# latch6.net
KiCad netlist of a schematic drawn in EAGLE
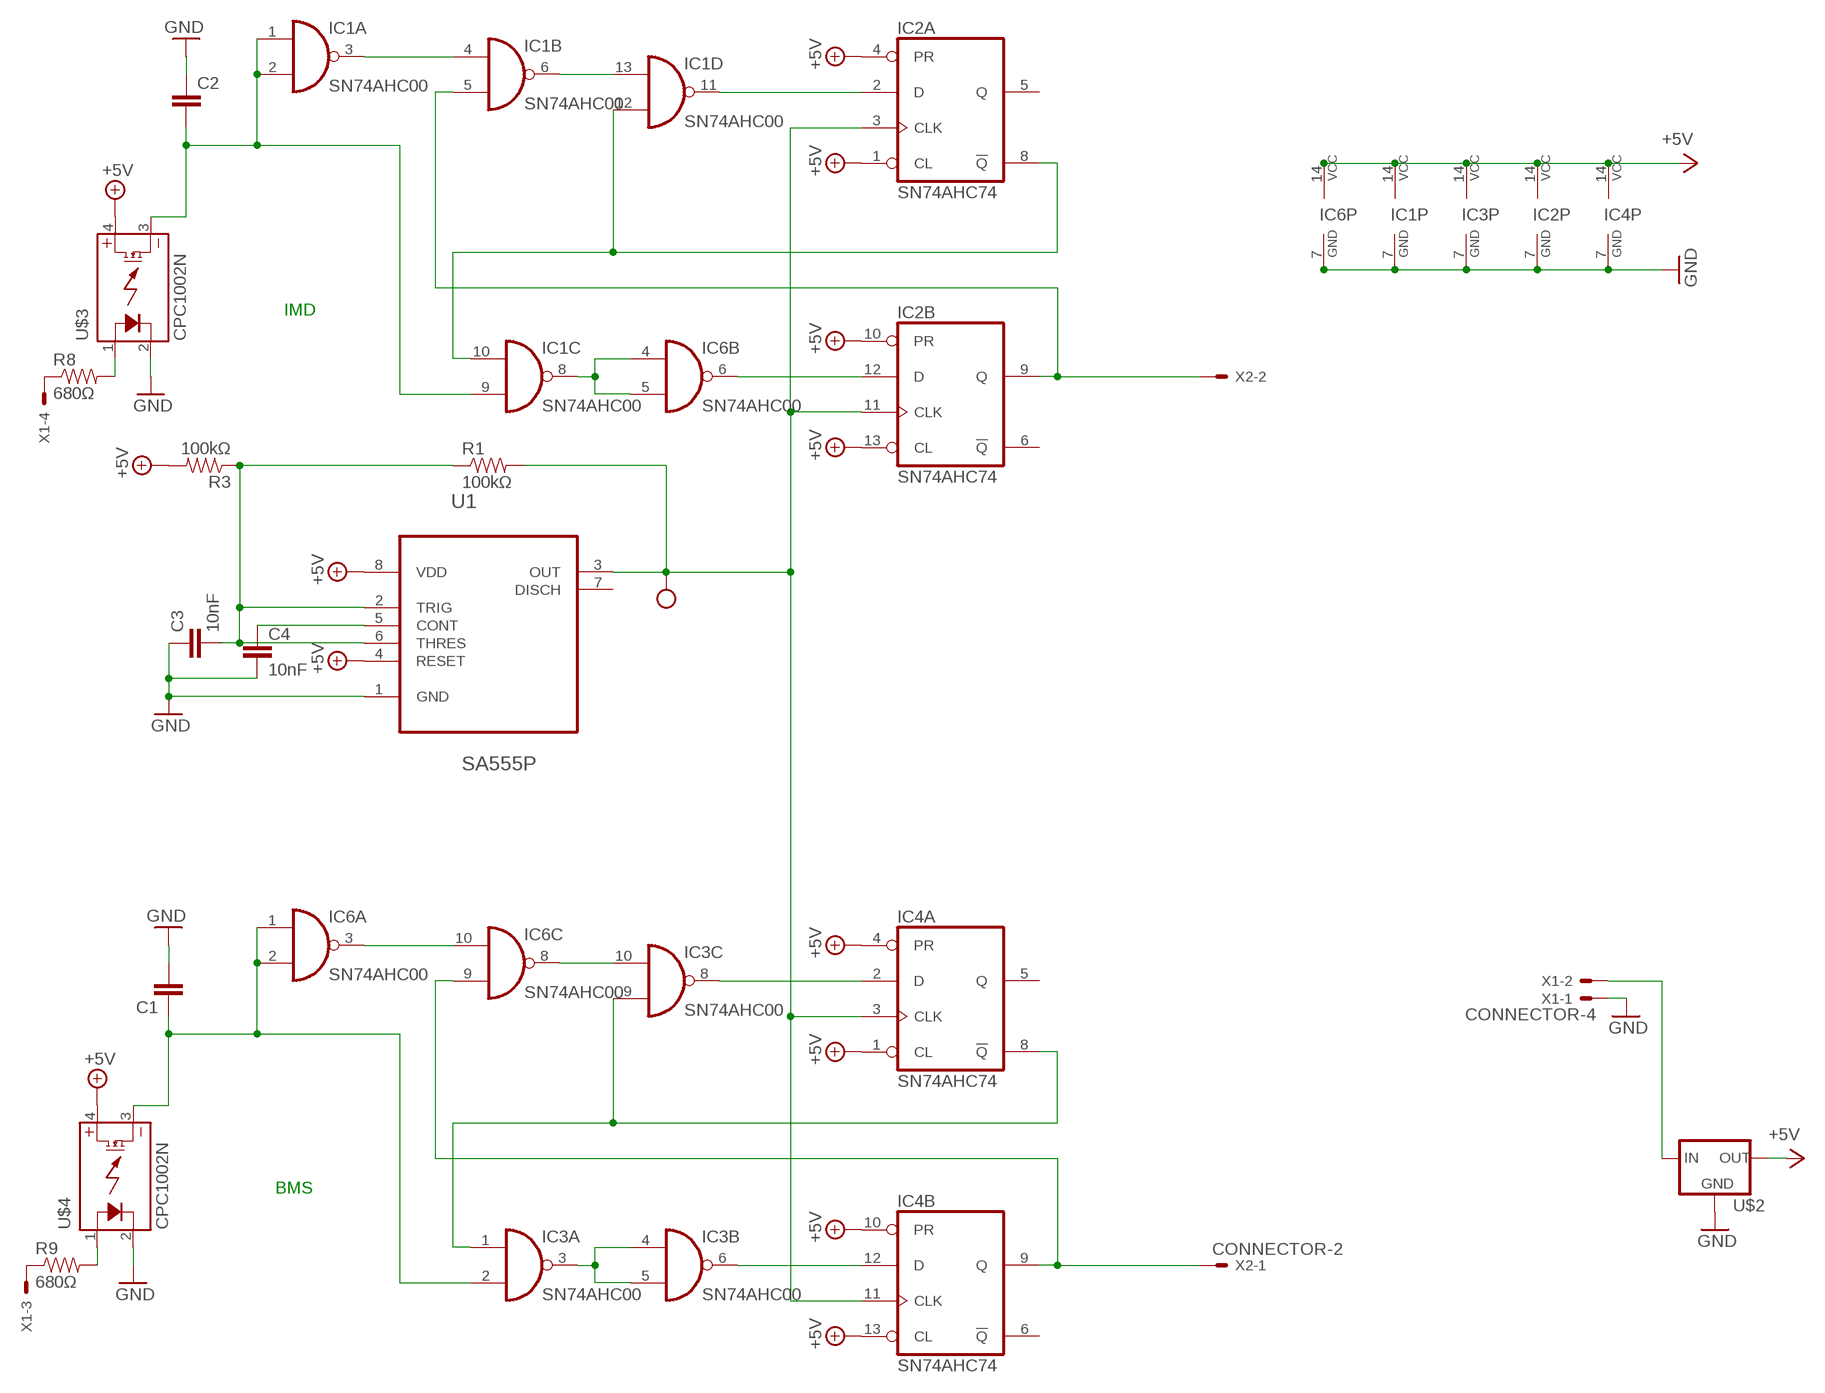
[diagram p0: schematic, sheet 1]

(export (version "E")
  (design (tool "Eeschema 10.0.6"))
  (components
    (comp (ref "C1")
      (value "CAP_")
      (footprint "eagle-import:AXIAL-5MM")
      (libsource (lib "eagle-import") (part "CAP_"))
    )
    (comp (ref "C2")
      (value "CAP_")
      (footprint "eagle-import:AXIAL-5MM")
      (libsource (lib "eagle-import") (part "CAP_"))
    )
    (comp (ref "C3")
      (value "10nF")
      (footprint "eagle-import:AXIAL-5MM")
      (libsource (lib "eagle-import") (part "CAP_"))
    )
    (comp (ref "C4")
      (value "10nF")
      (footprint "eagle-import:AXIAL-5MM")
      (libsource (lib "eagle-import") (part "CAP_"))
    )
    (comp (ref "IC1")
      (value "SN74AHC00")
      (footprint "eagle-import:DIL14")
      (libsource (lib "eagle-import") (part "SN74AHC00"))
    )
    (comp (ref "IC2")
      (value "SN74AHC74")
      (footprint "eagle-import:DIL14")
      (libsource (lib "eagle-import") (part "SN74AHC74"))
    )
    (comp (ref "IC3")
      (value "SN74AHC00")
      (footprint "eagle-import:DIL14")
      (libsource (lib "eagle-import") (part "SN74AHC00"))
    )
    (comp (ref "IC4")
      (value "SN74AHC74")
      (footprint "eagle-import:DIL14")
      (libsource (lib "eagle-import") (part "SN74AHC74"))
    )
    (comp (ref "IC6")
      (value "SN74AHC00")
      (footprint "eagle-import:DIL14")
      (libsource (lib "eagle-import") (part "SN74AHC00"))
    )
    (comp (ref "R1")
      (value "100kΩ")
      (footprint "eagle-import:AXIAL-0.4")
      (libsource (lib "eagle-import") (part "RESISTORPTH-1/4W"))
    )
    (comp (ref "R3")
      (value "100kΩ")
      (footprint "eagle-import:AXIAL-0.4")
      (libsource (lib "eagle-import") (part "RESISTORPTH-1/4W"))
    )
    (comp (ref "R8")
      (value "680Ω")
      (footprint "eagle-import:AXIAL-0.4")
      (libsource (lib "eagle-import") (part "RESISTORPTH-1/4W"))
    )
    (comp (ref "R9")
      (value "680Ω")
      (footprint "eagle-import:AXIAL-0.4")
      (libsource (lib "eagle-import") (part "RESISTORPTH-1/4W"))
    )
    (comp (ref "U$1")
      (value "TEST_POINT")
      (footprint "eagle-import:TEST_POINT")
      (libsource (lib "eagle-import") (part "TEST_POINT"))
    )
    (comp (ref "U$2")
      (value "5VREG_LM340-NLM340T-5.0/NOPB")
      (footprint "eagle-import:TO-220")
      (libsource (lib "eagle-import") (part "5VREG_LM340-NLM340T-5.0/NOPB"))
    )
    (comp (ref "U$3")
      (value "CPC1002N")
      (footprint "eagle-import:SOP04")
      (libsource (lib "eagle-import") (part "CPC1002N"))
    )
    (comp (ref "U$4")
      (value "CPC1002N")
      (footprint "eagle-import:SOP04")
      (libsource (lib "eagle-import") (part "CPC1002N"))
    )
    (comp (ref "U1")
      (value "SA555P")
      (footprint "eagle-import:DIP254P762X508-8")
      (libsource (lib "eagle-import") (part "SA555P"))
    )
    (comp (ref "X1")
      (value "CONNECTOR-4")
      (footprint "eagle-import:MINIFIT_5566-4")
      (libsource (lib "eagle-import") (part "CONNECTOR-4"))
    )
    (comp (ref "X2")
      (value "CONNECTOR-2")
      (footprint "eagle-import:MINIFIT_5566-2")
      (libsource (lib "eagle-import") (part "CONNECTOR-2"))
    )
  )
  (nets
    (net (code "1") (name "+5V") (class "Default")
      (node (ref "IC1") (pin "14") (pinfunction "VCC_14") (pintype "power_in"))
      (node (ref "IC2") (pin "1") (pinfunction "CL_1") (pintype "input"))
      (node (ref "IC2") (pin "10") (pinfunction "PR_10") (pintype "input"))
      (node (ref "IC2") (pin "13") (pinfunction "CL_13") (pintype "input"))
      (node (ref "IC2") (pin "14") (pinfunction "VCC_14") (pintype "power_in"))
      (node (ref "IC2") (pin "4") (pinfunction "PR_4") (pintype "input"))
      (node (ref "IC3") (pin "14") (pinfunction "VCC_14") (pintype "power_in"))
      (node (ref "IC4") (pin "1") (pinfunction "CL_1") (pintype "input"))
      (node (ref "IC4") (pin "10") (pinfunction "PR_10") (pintype "input"))
      (node (ref "IC4") (pin "13") (pinfunction "CL_13") (pintype "input"))
      (node (ref "IC4") (pin "14") (pinfunction "VCC_14") (pintype "power_in"))
      (node (ref "IC4") (pin "4") (pinfunction "PR_4") (pintype "input"))
      (node (ref "IC6") (pin "14") (pinfunction "VCC_14") (pintype "power_in"))
      (node (ref "R3") (pin "P$2") (pinfunction "2_P$2") (pintype "passive"))
      (node (ref "U$2") (pin "3") (pinfunction "OUT_3") (pintype "output"))
      (node (ref "U$3") (pin "4") (pinfunction "DC+_4") (pintype "passive"))
      (node (ref "U$4") (pin "4") (pinfunction "DC+_4") (pintype "passive"))
      (node (ref "U1") (pin "4") (pinfunction "RESET_4") (pintype "input"))
      (node (ref "U1") (pin "8") (pinfunction "VDD_8") (pintype "power_in"))
    )
    (net (code "2") (name "GND") (class "Default")
      (node (ref "C1") (pin "P$2") (pinfunction "2_P$2") (pintype "passive"))
      (node (ref "C2") (pin "P$1") (pinfunction "1_P$1") (pintype "passive"))
      (node (ref "C3") (pin "P$1") (pinfunction "1_P$1") (pintype "passive"))
      (node (ref "C4") (pin "P$2") (pinfunction "2_P$2") (pintype "passive"))
      (node (ref "IC1") (pin "7") (pinfunction "GND_7") (pintype "power_in"))
      (node (ref "IC2") (pin "7") (pinfunction "GND_7") (pintype "power_in"))
      (node (ref "IC3") (pin "7") (pinfunction "GND_7") (pintype "power_in"))
      (node (ref "IC4") (pin "7") (pinfunction "GND_7") (pintype "power_in"))
      (node (ref "IC6") (pin "7") (pinfunction "GND_7") (pintype "power_in"))
      (node (ref "U$2") (pin "2") (pinfunction "GND_2") (pintype "input"))
      (node (ref "U$3") (pin "2") (pinfunction "CONTROL-_2") (pintype "passive"))
      (node (ref "U$4") (pin "2") (pinfunction "CONTROL-_2") (pintype "passive"))
      (node (ref "U1") (pin "1") (pinfunction "GND_1") (pintype "passive"))
      (node (ref "X1") (pin "1") (pinfunction "S_1") (pintype "passive"))
    )
    (net (code "3") (name "Net-(C1-1)") (class "Default")
      (node (ref "C1") (pin "P$1") (pinfunction "1_P$1") (pintype "passive"))
      (node (ref "IC3") (pin "2") (pinfunction "I1_2") (pintype "input"))
      (node (ref "IC6") (pin "1") (pinfunction "I0_1") (pintype "input"))
      (node (ref "IC6") (pin "2") (pinfunction "I1_2") (pintype "input"))
      (node (ref "U$4") (pin "3") (pinfunction "DC-_3") (pintype "passive"))
    )
    (net (code "4") (name "Net-(C2-2)") (class "Default")
      (node (ref "C2") (pin "P$2") (pinfunction "2_P$2") (pintype "passive"))
      (node (ref "IC1") (pin "1") (pinfunction "I0_1") (pintype "input"))
      (node (ref "IC1") (pin "2") (pinfunction "I1_2") (pintype "input"))
      (node (ref "IC1") (pin "9") (pinfunction "I1_9") (pintype "input"))
      (node (ref "U$3") (pin "3") (pinfunction "DC-_3") (pintype "passive"))
    )
    (net (code "5") (name "Net-(C3-2)") (class "Default")
      (node (ref "C3") (pin "P$2") (pinfunction "2_P$2") (pintype "passive"))
      (node (ref "R1") (pin "P$1") (pinfunction "1_P$1") (pintype "passive"))
      (node (ref "R3") (pin "P$1") (pinfunction "1_P$1") (pintype "passive"))
      (node (ref "U1") (pin "2") (pinfunction "TRIG_2") (pintype "input"))
      (node (ref "U1") (pin "6") (pinfunction "THRES_6") (pintype "input"))
    )
    (net (code "6") (name "Net-(C4-1)") (class "Default")
      (node (ref "C4") (pin "P$1") (pinfunction "1_P$1") (pintype "passive"))
      (node (ref "U1") (pin "5") (pinfunction "CONT_5") (pintype "input"))
    )
    (net (code "7") (name "Net-(IC1A-O)") (class "Default")
      (node (ref "IC1") (pin "3") (pinfunction "O_3") (pintype "output"))
      (node (ref "IC1") (pin "4") (pinfunction "I0_4") (pintype "input"))
    )
    (net (code "8") (name "Net-(IC1B-I1)") (class "Default")
      (node (ref "IC1") (pin "5") (pinfunction "I1_5") (pintype "input"))
      (node (ref "IC2") (pin "9") (pinfunction "Q_9") (pintype "output"))
      (node (ref "X2") (pin "2") (pinfunction "S_2") (pintype "passive"))
    )
    (net (code "9") (name "Net-(IC1B-O)") (class "Default")
      (node (ref "IC1") (pin "13") (pinfunction "I0_13") (pintype "input"))
      (node (ref "IC1") (pin "6") (pinfunction "O_6") (pintype "output"))
    )
    (net (code "10") (name "Net-(IC1C-I0)") (class "Default")
      (node (ref "IC1") (pin "10") (pinfunction "I0_10") (pintype "input"))
      (node (ref "IC1") (pin "12") (pinfunction "I1_12") (pintype "input"))
      (node (ref "IC2") (pin "8") (pinfunction "~{Q}_8") (pintype "output"))
    )
    (net (code "11") (name "Net-(IC1C-O)") (class "Default")
      (node (ref "IC1") (pin "8") (pinfunction "O_8") (pintype "output"))
      (node (ref "IC6") (pin "4") (pinfunction "I0_4") (pintype "input"))
      (node (ref "IC6") (pin "5") (pinfunction "I1_5") (pintype "input"))
    )
    (net (code "12") (name "Net-(IC1D-O)") (class "Default")
      (node (ref "IC1") (pin "11") (pinfunction "O_11") (pintype "output"))
      (node (ref "IC2") (pin "2") (pinfunction "D_2") (pintype "input"))
    )
    (net (code "13") (name "Net-(IC2A-CLK)") (class "Default")
      (node (ref "IC2") (pin "11") (pinfunction "CLK_11") (pintype "input"))
      (node (ref "IC2") (pin "3") (pinfunction "CLK_3") (pintype "input"))
      (node (ref "IC4") (pin "11") (pinfunction "CLK_11") (pintype "input"))
      (node (ref "IC4") (pin "3") (pinfunction "CLK_3") (pintype "input"))
      (node (ref "R1") (pin "P$2") (pinfunction "2_P$2") (pintype "passive"))
      (node (ref "U$1") (pin "P$1") (pinfunction "P$1_P$1") (pintype "bidirectional"))
      (node (ref "U1") (pin "3") (pinfunction "OUT_3") (pintype "output"))
    )
    (net (code "14") (name "Net-(IC2B-D)") (class "Default")
      (node (ref "IC2") (pin "12") (pinfunction "D_12") (pintype "input"))
      (node (ref "IC6") (pin "6") (pinfunction "O_6") (pintype "output"))
    )
    (net (code "15") (name "Net-(IC3A-I0)") (class "Default")
      (node (ref "IC3") (pin "1") (pinfunction "I0_1") (pintype "input"))
      (node (ref "IC3") (pin "9") (pinfunction "I1_9") (pintype "input"))
      (node (ref "IC4") (pin "8") (pinfunction "~{Q}_8") (pintype "output"))
    )
    (net (code "16") (name "Net-(IC3A-O)") (class "Default")
      (node (ref "IC3") (pin "3") (pinfunction "O_3") (pintype "output"))
      (node (ref "IC3") (pin "4") (pinfunction "I0_4") (pintype "input"))
      (node (ref "IC3") (pin "5") (pinfunction "I1_5") (pintype "input"))
    )
    (net (code "17") (name "Net-(IC3B-O)") (class "Default")
      (node (ref "IC3") (pin "6") (pinfunction "O_6") (pintype "output"))
      (node (ref "IC4") (pin "12") (pinfunction "D_12") (pintype "input"))
    )
    (net (code "18") (name "Net-(IC3C-I0)") (class "Default")
      (node (ref "IC3") (pin "10") (pinfunction "I0_10") (pintype "input"))
      (node (ref "IC6") (pin "8") (pinfunction "O_8") (pintype "output"))
    )
    (net (code "19") (name "Net-(IC3C-O)") (class "Default")
      (node (ref "IC3") (pin "8") (pinfunction "O_8") (pintype "output"))
      (node (ref "IC4") (pin "2") (pinfunction "D_2") (pintype "input"))
    )
    (net (code "20") (name "Net-(IC4B-Q)") (class "Default")
      (node (ref "IC4") (pin "9") (pinfunction "Q_9") (pintype "output"))
      (node (ref "IC6") (pin "9") (pinfunction "I1_9") (pintype "input"))
      (node (ref "X2") (pin "1") (pinfunction "S_1") (pintype "passive"))
    )
    (net (code "21") (name "Net-(IC6A-O)") (class "Default")
      (node (ref "IC6") (pin "10") (pinfunction "I0_10") (pintype "input"))
      (node (ref "IC6") (pin "3") (pinfunction "O_3") (pintype "output"))
    )
    (net (code "22") (name "Net-(R8-1)") (class "Default")
      (node (ref "R8") (pin "P$1") (pinfunction "1_P$1") (pintype "passive"))
      (node (ref "X1") (pin "4") (pinfunction "S_4") (pintype "passive"))
    )
    (net (code "23") (name "Net-(R8-2)") (class "Default")
      (node (ref "R8") (pin "P$2") (pinfunction "2_P$2") (pintype "passive"))
      (node (ref "U$3") (pin "1") (pinfunction "CONTROL+_1") (pintype "passive"))
    )
    (net (code "24") (name "Net-(R9-1)") (class "Default")
      (node (ref "R9") (pin "P$1") (pinfunction "1_P$1") (pintype "passive"))
      (node (ref "X1") (pin "3") (pinfunction "S_3") (pintype "passive"))
    )
    (net (code "25") (name "Net-(R9-2)") (class "Default")
      (node (ref "R9") (pin "P$2") (pinfunction "2_P$2") (pintype "passive"))
      (node (ref "U$4") (pin "1") (pinfunction "CONTROL+_1") (pintype "passive"))
    )
    (net (code "26") (name "Net-(U$2-IN)") (class "Default")
      (node (ref "U$2") (pin "1") (pinfunction "IN_1") (pintype "input"))
      (node (ref "X1") (pin "2") (pinfunction "S_2") (pintype "passive"))
    )
    (net (code "27") (name "unconnected-(IC2A-Q-Pad5)") (class "Default")
      (node (ref "IC2") (pin "5") (pinfunction "Q_5") (pintype "output"))
    )
    (net (code "28") (name "unconnected-(IC2B-~{Q}-Pad6)") (class "Default")
      (node (ref "IC2") (pin "6") (pinfunction "~{Q}_6") (pintype "output"))
    )
    (net (code "29") (name "unconnected-(IC4A-Q-Pad5)") (class "Default")
      (node (ref "IC4") (pin "5") (pinfunction "Q_5") (pintype "output"))
    )
    (net (code "30") (name "unconnected-(IC4B-~{Q}-Pad6)") (class "Default")
      (node (ref "IC4") (pin "6") (pinfunction "~{Q}_6") (pintype "output"))
    )
    (net (code "31") (name "unconnected-(U1-DISCH-Pad7)") (class "Default")
      (node (ref "U1") (pin "7") (pinfunction "DISCH_7") (pintype "output"))
    )
  )
)
